# general.net
KiCad netlist of a schematic drawn in EAGLE
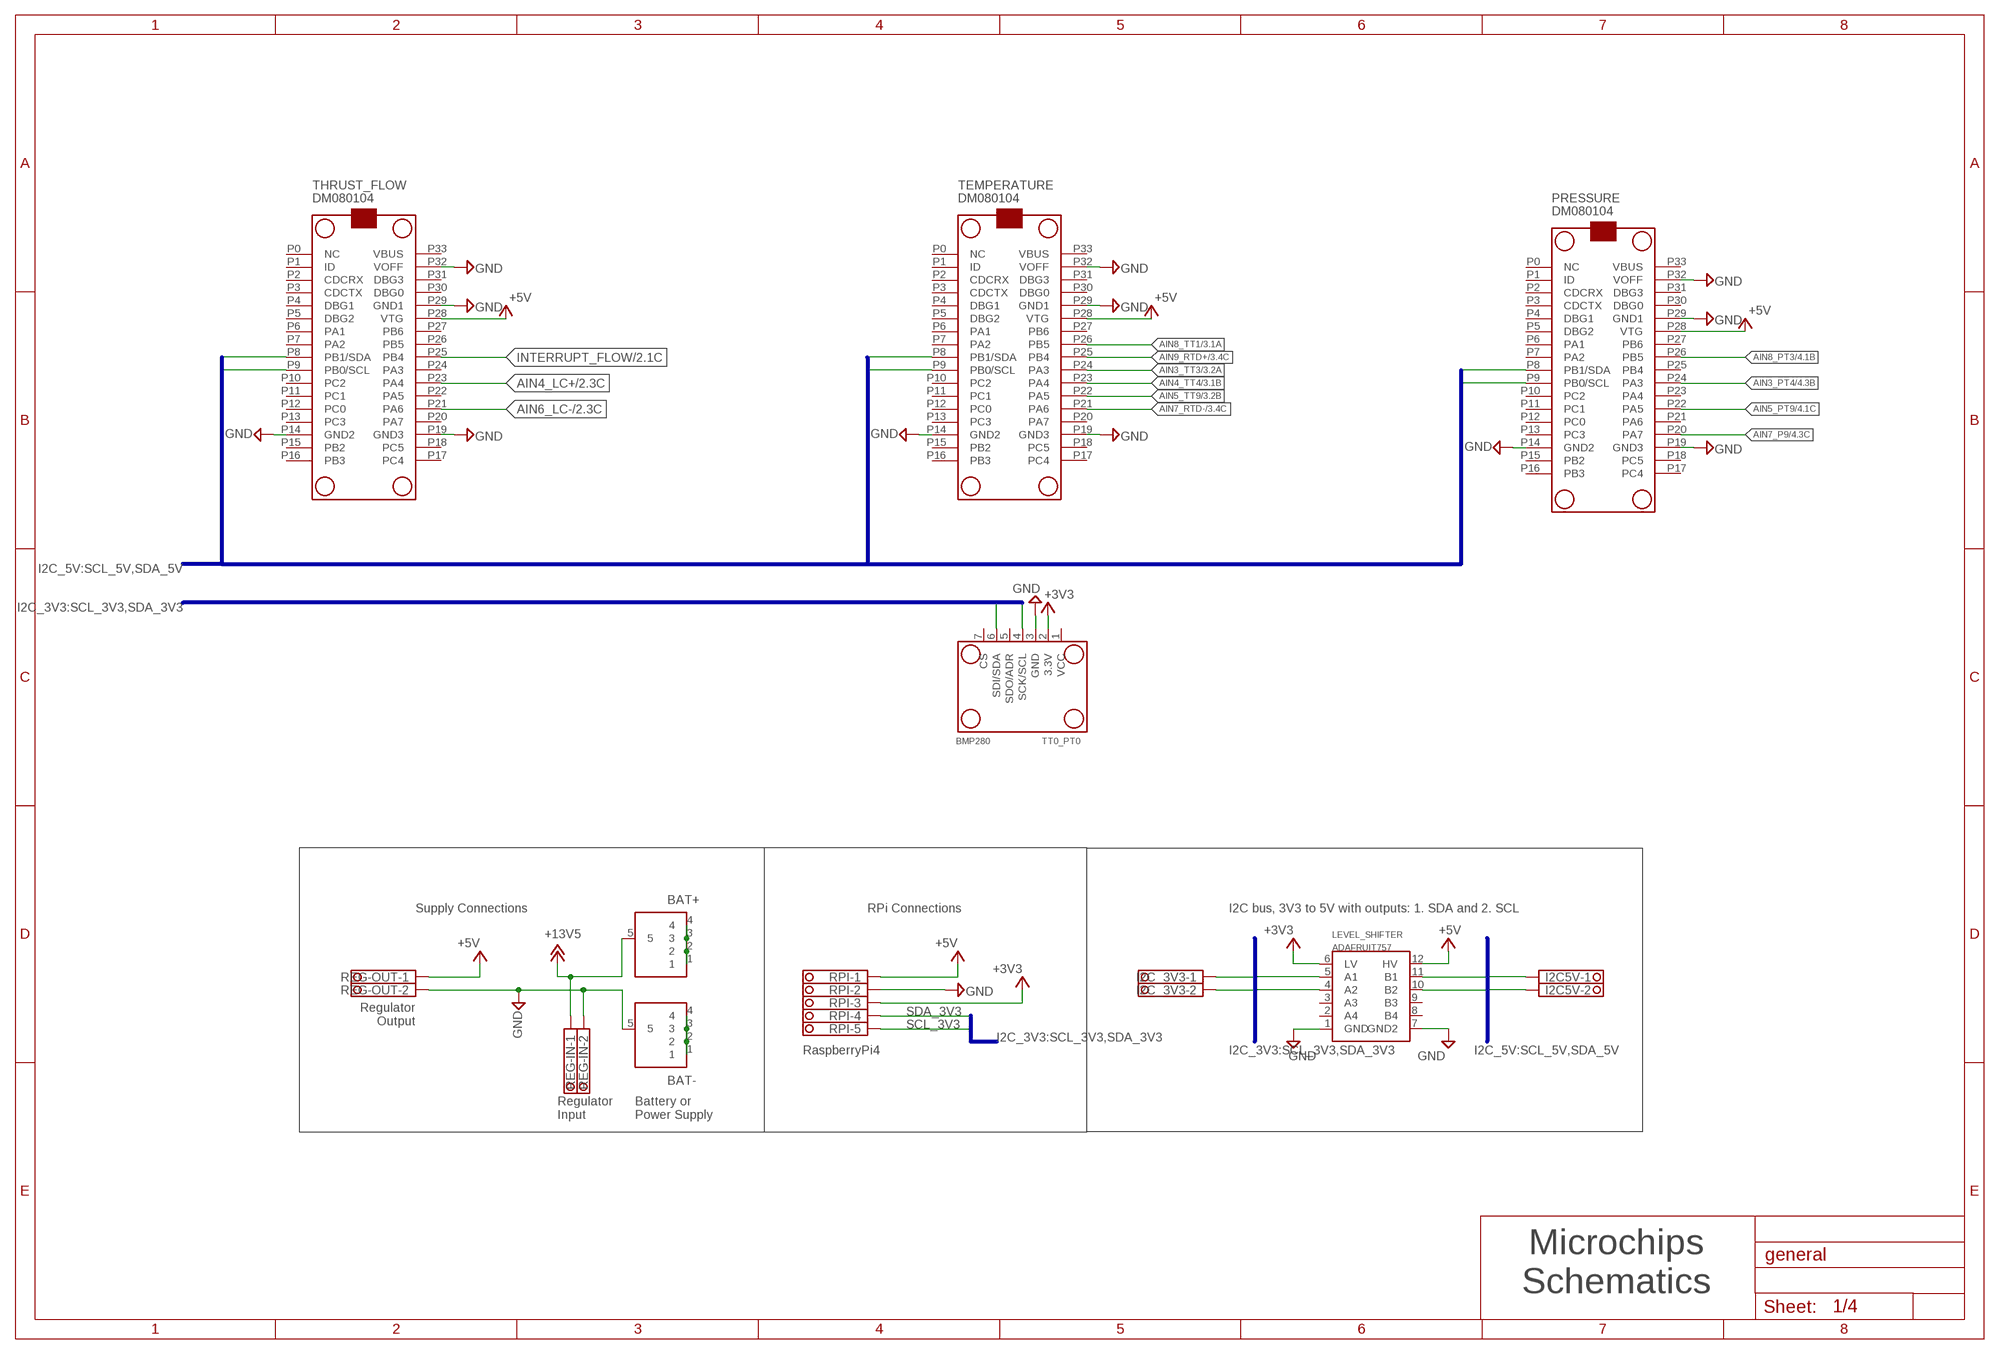
[diagram p0: schematic, sheet 1]
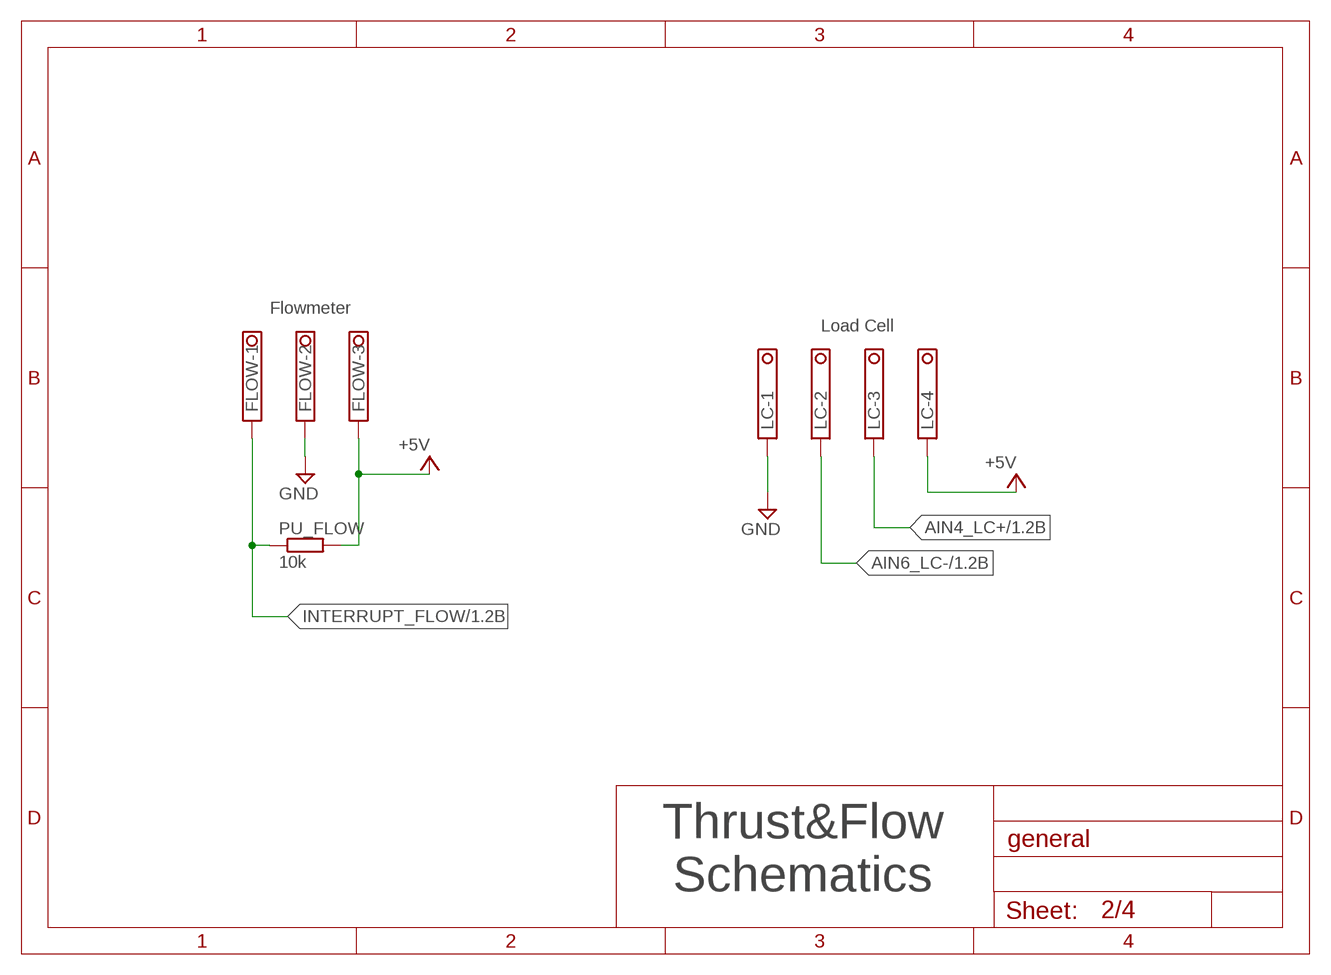
[diagram p1: schematic, sheet 2]
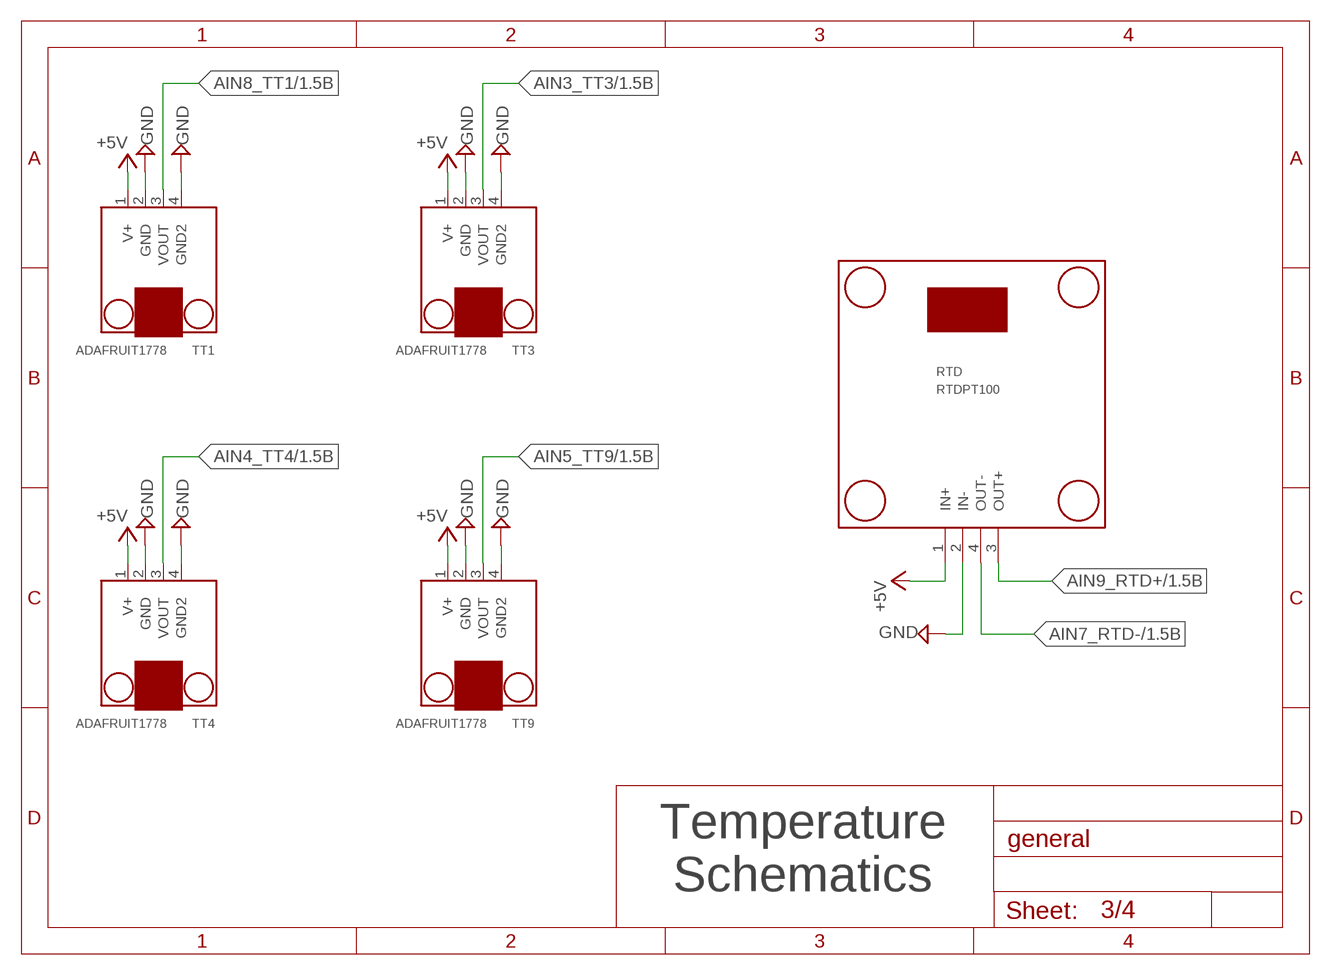
[diagram p2: schematic, sheet 3]
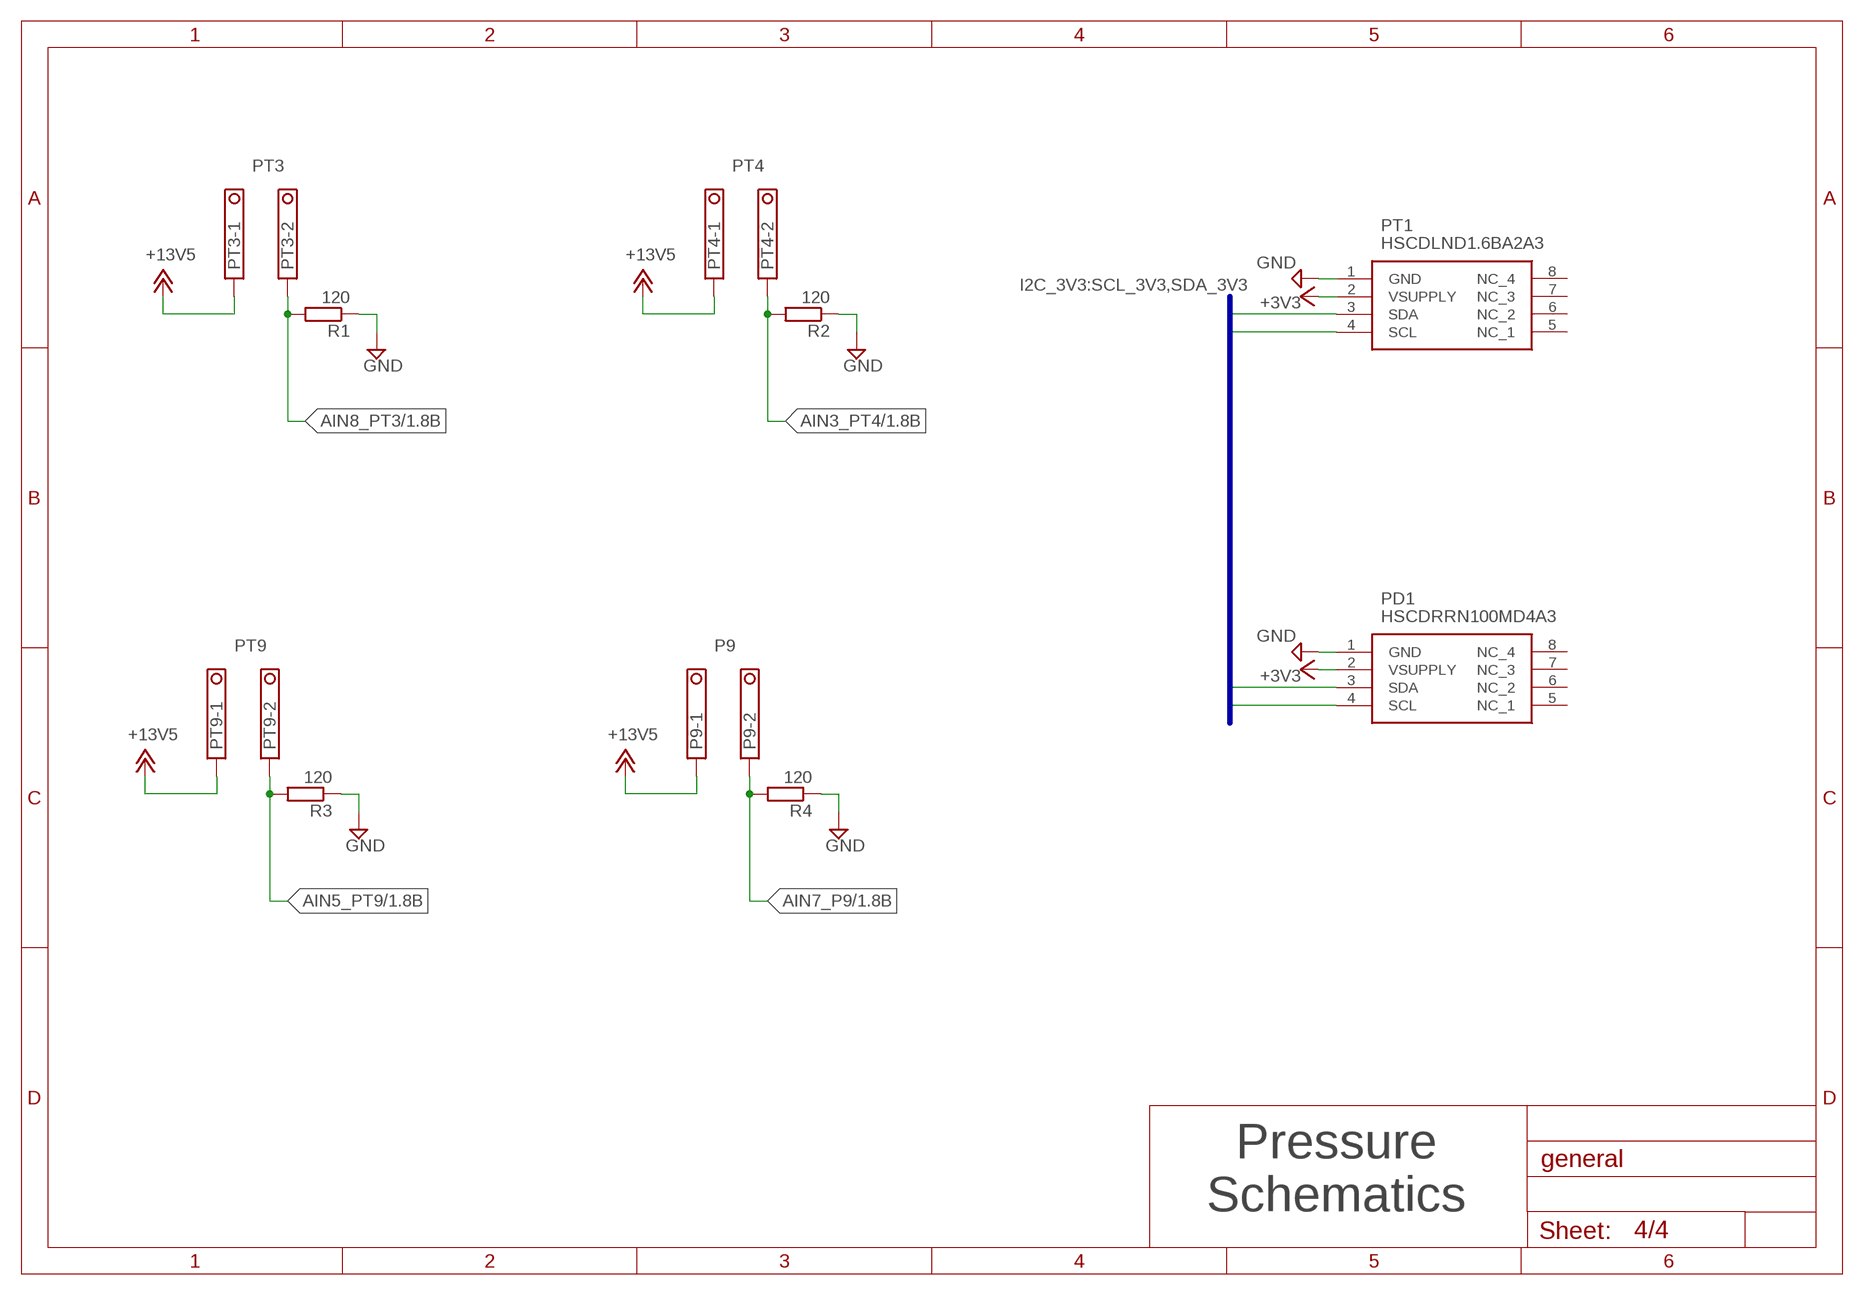
[diagram p3: schematic, sheet 4]

(export (version "E")
  (design (tool "Eeschema 10.0.6"))
  (components
    (comp (ref "RTD")
      (value "RTDPT100")
      (footprint "eagle-import:RTDPT100")
      (libsource (lib "eagle-import") (part "RTDPT100"))
    )
    (comp (ref "TT1")
      (value "ADAFRUIT1778")
      (footprint "eagle-import:ADAFRUIT1778")
      (libsource (lib "eagle-import") (part "ADAFRUIT1778"))
    )
    (comp (ref "TT3")
      (value "ADAFRUIT1778")
      (footprint "eagle-import:ADAFRUIT1778")
      (libsource (lib "eagle-import") (part "ADAFRUIT1778"))
    )
    (comp (ref "TT4")
      (value "ADAFRUIT1778")
      (footprint "eagle-import:ADAFRUIT1778")
      (libsource (lib "eagle-import") (part "ADAFRUIT1778"))
    )
    (comp (ref "TT9")
      (value "ADAFRUIT1778")
      (footprint "eagle-import:ADAFRUIT1778")
      (libsource (lib "eagle-import") (part "ADAFRUIT1778"))
    )
    (comp (ref "FLOW")
      (value "1751251")
      (footprint "eagle-import:1751251")
      (libsource (lib "eagle-import") (part "1751251"))
    )
    (comp (ref "LC")
      (value "1751264")
      (footprint "eagle-import:1751264")
      (libsource (lib "eagle-import") (part "1751264"))
    )
    (comp (ref "PU_FLOW")
      (value "10k")
      (footprint "eagle-import:0207_10")
      (libsource (lib "eagle-import") (part "R-EU_0207/10"))
    )
    (comp (ref "P9")
      (value "1751248")
      (footprint "eagle-import:1751248")
      (libsource (lib "eagle-import") (part "1751248"))
    )
    (comp (ref "PD1")
      (value "HSCDRRN100MD4A3")
      (footprint "eagle-import:HSCDRRN100MD4A3")
      (fields (field (name "MOUSER_PART_NUMBER") "785-HSCDRRN100MD4A3"))
      (libsource (lib "eagle-import") (part "HSCDRRN100MD4A3"))
    )
    (comp (ref "PT1")
      (value "HSCDLND1.6BA2A3")
      (footprint "eagle-import:HSCDLND1.6BA2A3")
      (libsource (lib "eagle-import") (part "HSCDLND1.6BA2A3"))
    )
    (comp (ref "PT3")
      (value "1751248")
      (footprint "eagle-import:1751248")
      (libsource (lib "eagle-import") (part "1751248"))
    )
    (comp (ref "PT4")
      (value "1751248")
      (footprint "eagle-import:1751248")
      (libsource (lib "eagle-import") (part "1751248"))
    )
    (comp (ref "PT9")
      (value "1751248")
      (footprint "eagle-import:1751248")
      (libsource (lib "eagle-import") (part "1751248"))
    )
    (comp (ref "R1")
      (value "120")
      (footprint "eagle-import:0207_10")
      (libsource (lib "eagle-import") (part "R-EU_0207/10"))
    )
    (comp (ref "R2")
      (value "120")
      (footprint "eagle-import:0207_10")
      (libsource (lib "eagle-import") (part "R-EU_0207/10"))
    )
    (comp (ref "R3")
      (value "120")
      (footprint "eagle-import:0207_10")
      (libsource (lib "eagle-import") (part "R-EU_0207/10"))
    )
    (comp (ref "R4")
      (value "120")
      (footprint "eagle-import:0207_10")
      (libsource (lib "eagle-import") (part "R-EU_0207/10"))
    )
    (comp (ref "BAT+")
      (value "73099-2730990")
      (footprint "eagle-import:730990")
      (libsource (lib "eagle-import") (part "73099-2730990"))
    )
    (comp (ref "BAT-")
      (value "73099-0")
      (footprint "eagle-import:730990")
      (fields (field (name "MOUSER_PART_NUMBER") "565-73099-0"))
      (libsource (lib "eagle-import") (part "73099-0"))
    )
    (comp (ref "I2C5V")
      (value "1751248")
      (footprint "eagle-import:1751248")
      (libsource (lib "eagle-import") (part "1751248"))
    )
    (comp (ref "I2C_3V3")
      (value "1751248")
      (footprint "eagle-import:1751248")
      (libsource (lib "eagle-import") (part "1751248"))
    )
    (comp (ref "LEVEL_SHIFTER")
      (value "ADAFRUIT757")
      (footprint "eagle-import:ADAFRUIT757")
      (libsource (lib "eagle-import") (part "ADAFRUIT757"))
    )
    (comp (ref "PRESSURE")
      (value "DM080104")
      (footprint "eagle-import:DM080104")
      (libsource (lib "eagle-import") (part "DM080104"))
    )
    (comp (ref "REG-IN")
      (value "1751248")
      (footprint "eagle-import:1751248")
      (libsource (lib "eagle-import") (part "1751248"))
    )
    (comp (ref "REG-OUT")
      (value "1751248")
      (footprint "eagle-import:1751248")
      (libsource (lib "eagle-import") (part "1751248"))
    )
    (comp (ref "RPI")
      (value "1751277")
      (footprint "eagle-import:1751277")
      (libsource (lib "eagle-import") (part "1751277"))
    )
    (comp (ref "TEMPERATURE")
      (value "DM080104")
      (footprint "eagle-import:DM080104")
      (libsource (lib "eagle-import") (part "DM080104"))
    )
    (comp (ref "THRUST_FLOW")
      (value "DM080104")
      (footprint "eagle-import:DM080104")
      (libsource (lib "eagle-import") (part "DM080104"))
    )
    (comp (ref "TT0_PT0")
      (value "BMP280")
      (footprint "eagle-import:BMP280")
      (libsource (lib "eagle-import") (part "BMP280"))
    )
  )
  (nets
    (net (code "4") (name "+3V3") (class "Default")
      (node (ref "LEVEL_SHIFTER") (pin "6") (pinfunction "LV_6") (pintype "bidirectional"))
      (node (ref "PD1") (pin "2") (pinfunction "VSUPPLY_2") (pintype "power_in"))
      (node (ref "PT1") (pin "2") (pinfunction "VSUPPLY_2") (pintype "power_in"))
      (node (ref "RPI") (pin "3") (pinfunction "K_3") (pintype "passive"))
      (node (ref "TT0_PT0") (pin "2") (pinfunction "3.3V_2") (pintype "power_in"))
    )
    (net (code "5") (name "+5V") (class "Default")
      (node (ref "FLOW") (pin "3") (pinfunction "K_3") (pintype "passive"))
      (node (ref "LC") (pin "4") (pinfunction "K_4") (pintype "passive"))
      (node (ref "LEVEL_SHIFTER") (pin "12") (pinfunction "HV_12") (pintype "bidirectional"))
      (node (ref "PRESSURE") (pin "P28") (pinfunction "VTG_P28") (pintype "power_in"))
      (node (ref "PU_FLOW") (pin "2") (pinfunction "2_2") (pintype "passive"))
      (node (ref "REG-OUT") (pin "1") (pinfunction "K_1") (pintype "passive"))
      (node (ref "RPI") (pin "1") (pinfunction "K_1") (pintype "passive"))
      (node (ref "RTD") (pin "1") (pinfunction "IN+_1") (pintype "input"))
      (node (ref "TEMPERATURE") (pin "P28") (pinfunction "VTG_P28") (pintype "power_in"))
      (node (ref "THRUST_FLOW") (pin "P28") (pinfunction "VTG_P28") (pintype "power_in"))
      (node (ref "TT1") (pin "1") (pinfunction "V+_1") (pintype "power_in"))
      (node (ref "TT3") (pin "1") (pinfunction "V+_1") (pintype "power_in"))
      (node (ref "TT4") (pin "1") (pinfunction "V+_1") (pintype "power_in"))
      (node (ref "TT9") (pin "1") (pinfunction "V+_1") (pintype "power_in"))
    )
    (net (code "6") (name "+13V5") (class "Default")
      (node (ref "BAT+") (pin "5") (pinfunction "5_5") (pintype "bidirectional"))
      (node (ref "P9") (pin "1") (pinfunction "K_1") (pintype "passive"))
      (node (ref "PT3") (pin "1") (pinfunction "K_1") (pintype "passive"))
      (node (ref "PT4") (pin "1") (pinfunction "K_1") (pintype "passive"))
      (node (ref "PT9") (pin "1") (pinfunction "K_1") (pintype "passive"))
      (node (ref "REG-IN") (pin "1") (pinfunction "K_1") (pintype "passive"))
    )
    (net (code "10") (name "AIN3_PT4") (class "Default")
      (node (ref "PRESSURE") (pin "P24") (pinfunction "PA3_P24") (pintype "bidirectional"))
      (node (ref "PT4") (pin "2") (pinfunction "K_2") (pintype "passive"))
      (node (ref "R2") (pin "2") (pinfunction "2_2") (pintype "passive"))
    )
    (net (code "11") (name "AIN3_TT3") (class "Default")
      (node (ref "TEMPERATURE") (pin "P24") (pinfunction "PA3_P24") (pintype "bidirectional"))
      (node (ref "TT3") (pin "3") (pinfunction "VOUT_3") (pintype "output"))
    )
    (net (code "12") (name "AIN4_LC+") (class "Default")
      (node (ref "LC") (pin "3") (pinfunction "K_3") (pintype "passive"))
      (node (ref "THRUST_FLOW") (pin "P23") (pinfunction "PA4_P23") (pintype "bidirectional"))
    )
    (net (code "13") (name "AIN4_TT4") (class "Default")
      (node (ref "TEMPERATURE") (pin "P23") (pinfunction "PA4_P23") (pintype "bidirectional"))
      (node (ref "TT4") (pin "3") (pinfunction "VOUT_3") (pintype "output"))
    )
    (net (code "14") (name "AIN5_PT9") (class "Default")
      (node (ref "PRESSURE") (pin "P22") (pinfunction "PA5_P22") (pintype "bidirectional"))
      (node (ref "PT9") (pin "2") (pinfunction "K_2") (pintype "passive"))
      (node (ref "R3") (pin "2") (pinfunction "2_2") (pintype "passive"))
    )
    (net (code "15") (name "AIN5_TT9") (class "Default")
      (node (ref "TEMPERATURE") (pin "P22") (pinfunction "PA5_P22") (pintype "bidirectional"))
      (node (ref "TT9") (pin "3") (pinfunction "VOUT_3") (pintype "output"))
    )
    (net (code "16") (name "AIN6_LC-") (class "Default")
      (node (ref "LC") (pin "2") (pinfunction "K_2") (pintype "passive"))
      (node (ref "THRUST_FLOW") (pin "P21") (pinfunction "PA6_P21") (pintype "bidirectional"))
    )
    (net (code "17") (name "AIN7_P9") (class "Default")
      (node (ref "P9") (pin "2") (pinfunction "K_2") (pintype "passive"))
      (node (ref "PRESSURE") (pin "P20") (pinfunction "PA7_P20") (pintype "bidirectional"))
      (node (ref "R4") (pin "2") (pinfunction "2_2") (pintype "passive"))
    )
    (net (code "18") (name "AIN7_RTD-") (class "Default")
      (node (ref "RTD") (pin "4") (pinfunction "OUT-_4") (pintype "output"))
      (node (ref "TEMPERATURE") (pin "P21") (pinfunction "PA6_P21") (pintype "bidirectional"))
    )
    (net (code "19") (name "AIN8_PT3") (class "Default")
      (node (ref "PRESSURE") (pin "P26") (pinfunction "PB5_P26") (pintype "bidirectional"))
      (node (ref "PT3") (pin "2") (pinfunction "K_2") (pintype "passive"))
      (node (ref "R1") (pin "2") (pinfunction "2_2") (pintype "passive"))
    )
    (net (code "20") (name "AIN8_TT1") (class "Default")
      (node (ref "TEMPERATURE") (pin "P26") (pinfunction "PB5_P26") (pintype "bidirectional"))
      (node (ref "TT1") (pin "3") (pinfunction "VOUT_3") (pintype "output"))
    )
    (net (code "21") (name "AIN9_RTD+") (class "Default")
      (node (ref "RTD") (pin "3") (pinfunction "OUT+_3") (pintype "output"))
      (node (ref "TEMPERATURE") (pin "P25") (pinfunction "PB4_P25") (pintype "bidirectional"))
    )
    (net (code "22") (name "GND") (class "Default")
      (node (ref "BAT-") (pin "5") (pinfunction "5_5") (pintype "bidirectional"))
      (node (ref "FLOW") (pin "2") (pinfunction "K_2") (pintype "passive"))
      (node (ref "LC") (pin "1") (pinfunction "K_1") (pintype "passive"))
      (node (ref "LEVEL_SHIFTER") (pin "1") (pinfunction "GND_1") (pintype "bidirectional"))
      (node (ref "LEVEL_SHIFTER") (pin "7") (pinfunction "GND2_7") (pintype "bidirectional"))
      (node (ref "PD1") (pin "1") (pinfunction "GND_1") (pintype "power_in"))
      (node (ref "PRESSURE") (pin "P14") (pinfunction "GND2_P14") (pintype "bidirectional"))
      (node (ref "PRESSURE") (pin "P19") (pinfunction "GND3_P19") (pintype "bidirectional"))
      (node (ref "PRESSURE") (pin "P29") (pinfunction "GND1_P29") (pintype "power_in"))
      (node (ref "PRESSURE") (pin "P32") (pinfunction "VOFF_P32") (pintype "power_in"))
      (node (ref "PT1") (pin "1") (pinfunction "GND_1") (pintype "power_in"))
      (node (ref "R1") (pin "1") (pinfunction "1_1") (pintype "passive"))
      (node (ref "R2") (pin "1") (pinfunction "1_1") (pintype "passive"))
      (node (ref "R3") (pin "1") (pinfunction "1_1") (pintype "passive"))
      (node (ref "R4") (pin "1") (pinfunction "1_1") (pintype "passive"))
      (node (ref "REG-IN") (pin "2") (pinfunction "K_2") (pintype "passive"))
      (node (ref "REG-OUT") (pin "2") (pinfunction "K_2") (pintype "passive"))
      (node (ref "RPI") (pin "2") (pinfunction "K_2") (pintype "passive"))
      (node (ref "RTD") (pin "2") (pinfunction "IN-_2") (pintype "input"))
      (node (ref "TEMPERATURE") (pin "P14") (pinfunction "GND2_P14") (pintype "bidirectional"))
      (node (ref "TEMPERATURE") (pin "P19") (pinfunction "GND3_P19") (pintype "bidirectional"))
      (node (ref "TEMPERATURE") (pin "P29") (pinfunction "GND1_P29") (pintype "power_in"))
      (node (ref "TEMPERATURE") (pin "P32") (pinfunction "VOFF_P32") (pintype "power_in"))
      (node (ref "THRUST_FLOW") (pin "P14") (pinfunction "GND2_P14") (pintype "bidirectional"))
      (node (ref "THRUST_FLOW") (pin "P19") (pinfunction "GND3_P19") (pintype "bidirectional"))
      (node (ref "THRUST_FLOW") (pin "P29") (pinfunction "GND1_P29") (pintype "power_in"))
      (node (ref "THRUST_FLOW") (pin "P32") (pinfunction "VOFF_P32") (pintype "power_in"))
      (node (ref "TT0_PT0") (pin "3") (pinfunction "GND_3") (pintype "power_in"))
      (node (ref "TT1") (pin "2") (pinfunction "GND_2") (pintype "power_in"))
      (node (ref "TT1") (pin "4") (pinfunction "GND2_4") (pintype "power_in"))
      (node (ref "TT3") (pin "2") (pinfunction "GND_2") (pintype "power_in"))
      (node (ref "TT3") (pin "4") (pinfunction "GND2_4") (pintype "power_in"))
      (node (ref "TT4") (pin "2") (pinfunction "GND_2") (pintype "power_in"))
      (node (ref "TT4") (pin "4") (pinfunction "GND2_4") (pintype "power_in"))
      (node (ref "TT9") (pin "2") (pinfunction "GND_2") (pintype "power_in"))
      (node (ref "TT9") (pin "4") (pinfunction "GND2_4") (pintype "power_in"))
    )
    (net (code "23") (name "INTERRUPT_FLOW") (class "Default")
      (node (ref "FLOW") (pin "1") (pinfunction "K_1") (pintype "passive"))
      (node (ref "PU_FLOW") (pin "1") (pinfunction "1_1") (pintype "passive"))
      (node (ref "THRUST_FLOW") (pin "P25") (pinfunction "PB4_P25") (pintype "bidirectional"))
    )
    (net (code "24") (name "Net-(BAT+-Pad1)") (class "Default")
      (node (ref "BAT+") (pin "1") (pinfunction "1_1") (pintype "bidirectional"))
      (node (ref "BAT+") (pin "2") (pinfunction "2_2") (pintype "bidirectional"))
      (node (ref "BAT+") (pin "3") (pinfunction "3_3") (pintype "bidirectional"))
      (node (ref "BAT+") (pin "4") (pinfunction "4_4") (pintype "bidirectional"))
    )
    (net (code "25") (name "Net-(BAT--Pad1)") (class "Default")
      (node (ref "BAT-") (pin "1") (pinfunction "1_1") (pintype "bidirectional"))
      (node (ref "BAT-") (pin "2") (pinfunction "2_2") (pintype "bidirectional"))
      (node (ref "BAT-") (pin "3") (pinfunction "3_3") (pintype "bidirectional"))
      (node (ref "BAT-") (pin "4") (pinfunction "4_4") (pintype "bidirectional"))
    )
    (net (code "26") (name "SCL_3V3") (class "Default")
      (node (ref "I2C_3V3") (pin "2") (pinfunction "K_2") (pintype "passive"))
      (node (ref "LEVEL_SHIFTER") (pin "4") (pinfunction "A2_4") (pintype "bidirectional"))
      (node (ref "PD1") (pin "4") (pinfunction "SCL_4") (pintype "bidirectional"))
      (node (ref "PT1") (pin "4") (pinfunction "SCL_4") (pintype "bidirectional"))
      (node (ref "RPI") (pin "5") (pinfunction "K_5") (pintype "passive"))
      (node (ref "TT0_PT0") (pin "4") (pinfunction "SCK/SCL_4") (pintype "bidirectional"))
    )
    (net (code "27") (name "SCL_5V") (class "Default")
      (node (ref "I2C5V") (pin "2") (pinfunction "K_2") (pintype "passive"))
      (node (ref "LEVEL_SHIFTER") (pin "10") (pinfunction "B2_10") (pintype "bidirectional"))
      (node (ref "PRESSURE") (pin "P9") (pinfunction "PB0/SCL_P9") (pintype "bidirectional"))
      (node (ref "TEMPERATURE") (pin "P9") (pinfunction "PB0/SCL_P9") (pintype "bidirectional"))
      (node (ref "THRUST_FLOW") (pin "P9") (pinfunction "PB0/SCL_P9") (pintype "bidirectional"))
    )
    (net (code "28") (name "SDA_3V3") (class "Default")
      (node (ref "I2C_3V3") (pin "1") (pinfunction "K_1") (pintype "passive"))
      (node (ref "LEVEL_SHIFTER") (pin "5") (pinfunction "A1_5") (pintype "bidirectional"))
      (node (ref "PD1") (pin "3") (pinfunction "SDA_3") (pintype "bidirectional"))
      (node (ref "PT1") (pin "3") (pinfunction "SDA_3") (pintype "bidirectional"))
      (node (ref "RPI") (pin "4") (pinfunction "K_4") (pintype "passive"))
      (node (ref "TT0_PT0") (pin "6") (pinfunction "SDI/SDA_6") (pintype "bidirectional"))
    )
    (net (code "29") (name "SDA_5V") (class "Default")
      (node (ref "I2C5V") (pin "1") (pinfunction "K_1") (pintype "passive"))
      (node (ref "LEVEL_SHIFTER") (pin "11") (pinfunction "B1_11") (pintype "bidirectional"))
      (node (ref "PRESSURE") (pin "P8") (pinfunction "PB1/SDA_P8") (pintype "bidirectional"))
      (node (ref "TEMPERATURE") (pin "P8") (pinfunction "PB1/SDA_P8") (pintype "bidirectional"))
      (node (ref "THRUST_FLOW") (pin "P8") (pinfunction "PB1/SDA_P8") (pintype "bidirectional"))
    )
    (net (code "30") (name "VCC") (class "Default")
      (node (ref "TT0_PT0") (pin "1") (pinfunction "VCC_1") (pintype "power_in"))
    )
    (net (code "31") (name "unconnected-(LEVEL_SHIFTER-A3-Pad3)") (class "Default")
      (node (ref "LEVEL_SHIFTER") (pin "3") (pinfunction "A3_3") (pintype "bidirectional"))
    )
    (net (code "32") (name "unconnected-(LEVEL_SHIFTER-A4-Pad2)") (class "Default")
      (node (ref "LEVEL_SHIFTER") (pin "2") (pinfunction "A4_2") (pintype "bidirectional"))
    )
    (net (code "33") (name "unconnected-(LEVEL_SHIFTER-B3-Pad9)") (class "Default")
      (node (ref "LEVEL_SHIFTER") (pin "9") (pinfunction "B3_9") (pintype "bidirectional"))
    )
    (net (code "34") (name "unconnected-(LEVEL_SHIFTER-B4-Pad8)") (class "Default")
      (node (ref "LEVEL_SHIFTER") (pin "8") (pinfunction "B4_8") (pintype "bidirectional"))
    )
    (net (code "35") (name "unconnected-(PD1-NC_1-Pad5)") (class "Default")
      (node (ref "PD1") (pin "5") (pinfunction "NC_1_5") (pintype "no_connect"))
    )
    (net (code "36") (name "unconnected-(PD1-NC_2-Pad6)") (class "Default")
      (node (ref "PD1") (pin "6") (pinfunction "NC_2_6") (pintype "no_connect"))
    )
    (net (code "37") (name "unconnected-(PD1-NC_3-Pad7)") (class "Default")
      (node (ref "PD1") (pin "7") (pinfunction "NC_3_7") (pintype "no_connect"))
    )
    (net (code "38") (name "unconnected-(PD1-NC_4-Pad8)") (class "Default")
      (node (ref "PD1") (pin "8") (pinfunction "NC_4_8") (pintype "no_connect"))
    )
    (net (code "39") (name "unconnected-(PRESSURE-CDCRX-PadP2)") (class "Default")
      (node (ref "PRESSURE") (pin "P2") (pinfunction "CDCRX_P2") (pintype "bidirectional"))
    )
    (net (code "40") (name "unconnected-(PRESSURE-CDCTX-PadP3)") (class "Default")
      (node (ref "PRESSURE") (pin "P3") (pinfunction "CDCTX_P3") (pintype "bidirectional"))
    )
    (net (code "41") (name "unconnected-(PRESSURE-DBG0-PadP30)") (class "Default")
      (node (ref "PRESSURE") (pin "P30") (pinfunction "DBG0_P30") (pintype "no_connect"))
    )
    (net (code "42") (name "unconnected-(PRESSURE-DBG1-PadP4)") (class "Default")
      (node (ref "PRESSURE") (pin "P4") (pinfunction "DBG1_P4") (pintype "no_connect"))
    )
    (net (code "43") (name "unconnected-(PRESSURE-DBG2-PadP5)") (class "Default")
      (node (ref "PRESSURE") (pin "P5") (pinfunction "DBG2_P5") (pintype "no_connect"))
    )
    (net (code "44") (name "unconnected-(PRESSURE-DBG3-PadP31)") (class "Default")
      (node (ref "PRESSURE") (pin "P31") (pinfunction "DBG3_P31") (pintype "no_connect"))
    )
    (net (code "45") (name "unconnected-(PRESSURE-ID-PadP1)") (class "Default")
      (node (ref "PRESSURE") (pin "P1") (pinfunction "ID_P1") (pintype "output"))
    )
    (net (code "46") (name "unconnected-(PRESSURE-NC-PadP0)") (class "Default")
      (node (ref "PRESSURE") (pin "P0") (pinfunction "NC_P0") (pintype "no_connect"))
    )
    (net (code "47") (name "unconnected-(PRESSURE-PA1-PadP6)") (class "Default")
      (node (ref "PRESSURE") (pin "P6") (pinfunction "PA1_P6") (pintype "bidirectional"))
    )
    (net (code "48") (name "unconnected-(PRESSURE-PA2-PadP7)") (class "Default")
      (node (ref "PRESSURE") (pin "P7") (pinfunction "PA2_P7") (pintype "bidirectional"))
    )
    (net (code "49") (name "unconnected-(PRESSURE-PA4-PadP23)") (class "Default")
      (node (ref "PRESSURE") (pin "P23") (pinfunction "PA4_P23") (pintype "bidirectional"))
    )
    (net (code "50") (name "unconnected-(PRESSURE-PA6-PadP21)") (class "Default")
      (node (ref "PRESSURE") (pin "P21") (pinfunction "PA6_P21") (pintype "bidirectional"))
    )
    (net (code "51") (name "unconnected-(PRESSURE-PB2-PadP15)") (class "Default")
      (node (ref "PRESSURE") (pin "P15") (pinfunction "PB2_P15") (pintype "bidirectional"))
    )
    (net (code "52") (name "unconnected-(PRESSURE-PB3-PadP16)") (class "Default")
      (node (ref "PRESSURE") (pin "P16") (pinfunction "PB3_P16") (pintype "bidirectional"))
    )
    (net (code "53") (name "unconnected-(PRESSURE-PB4-PadP25)") (class "Default")
      (node (ref "PRESSURE") (pin "P25") (pinfunction "PB4_P25") (pintype "bidirectional"))
    )
    (net (code "54") (name "unconnected-(PRESSURE-PB6-PadP27)") (class "Default")
      (node (ref "PRESSURE") (pin "P27") (pinfunction "PB6_P27") (pintype "bidirectional"))
    )
    (net (code "55") (name "unconnected-(PRESSURE-PC0-PadP12)") (class "Default")
      (node (ref "PRESSURE") (pin "P12") (pinfunction "PC0_P12") (pintype "bidirectional"))
    )
    (net (code "56") (name "unconnected-(PRESSURE-PC1-PadP11)") (class "Default")
      (node (ref "PRESSURE") (pin "P11") (pinfunction "PC1_P11") (pintype "bidirectional"))
    )
    (net (code "57") (name "unconnected-(PRESSURE-PC2-PadP10)") (class "Default")
      (node (ref "PRESSURE") (pin "P10") (pinfunction "PC2_P10") (pintype "bidirectional"))
    )
    (net (code "58") (name "unconnected-(PRESSURE-PC3-PadP13)") (class "Default")
      (node (ref "PRESSURE") (pin "P13") (pinfunction "PC3_P13") (pintype "bidirectional"))
    )
    (net (code "59") (name "unconnected-(PRESSURE-PC4-PadP17)") (class "Default")
      (node (ref "PRESSURE") (pin "P17") (pinfunction "PC4_P17") (pintype "bidirectional"))
    )
    (net (code "60") (name "unconnected-(PRESSURE-PC5-PadP18)") (class "Default")
      (node (ref "PRESSURE") (pin "P18") (pinfunction "PC5_P18") (pintype "bidirectional"))
    )
    (net (code "61") (name "unconnected-(PRESSURE-VBUS-PadP33)") (class "Default")
      (node (ref "PRESSURE") (pin "P33") (pinfunction "VBUS_P33") (pintype "output"))
    )
    (net (code "62") (name "unconnected-(PT1-NC_1-Pad5)") (class "Default")
      (node (ref "PT1") (pin "5") (pinfunction "NC_1_5") (pintype "no_connect"))
    )
    (net (code "63") (name "unconnected-(PT1-NC_2-Pad6)") (class "Default")
      (node (ref "PT1") (pin "6") (pinfunction "NC_2_6") (pintype "no_connect"))
    )
    (net (code "64") (name "unconnected-(PT1-NC_3-Pad7)") (class "Default")
      (node (ref "PT1") (pin "7") (pinfunction "NC_3_7") (pintype "no_connect"))
    )
    (net (code "65") (name "unconnected-(PT1-NC_4-Pad8)") (class "Default")
      (node (ref "PT1") (pin "8") (pinfunction "NC_4_8") (pintype "no_connect"))
    )
    (net (code "66") (name "unconnected-(TEMPERATURE-CDCRX-PadP2)") (class "Default")
      (node (ref "TEMPERATURE") (pin "P2") (pinfunction "CDCRX_P2") (pintype "bidirectional"))
    )
    (net (code "67") (name "unconnected-(TEMPERATURE-CDCTX-PadP3)") (class "Default")
      (node (ref "TEMPERATURE") (pin "P3") (pinfunction "CDCTX_P3") (pintype "bidirectional"))
    )
    (net (code "68") (name "unconnected-(TEMPERATURE-DBG0-PadP30)") (class "Default")
      (node (ref "TEMPERATURE") (pin "P30") (pinfunction "DBG0_P30") (pintype "no_connect"))
    )
    (net (code "69") (name "unconnected-(TEMPERATURE-DBG1-PadP4)") (class "Default")
      (node (ref "TEMPERATURE") (pin "P4") (pinfunction "DBG1_P4") (pintype "no_connect"))
    )
    (net (code "70") (name "unconnected-(TEMPERATURE-DBG2-PadP5)") (class "Default")
      (node (ref "TEMPERATURE") (pin "P5") (pinfunction "DBG2_P5") (pintype "no_connect"))
    )
    (net (code "71") (name "unconnected-(TEMPERATURE-DBG3-PadP31)") (class "Default")
      (node (ref "TEMPERATURE") (pin "P31") (pinfunction "DBG3_P31") (pintype "no_connect"))
    )
    (net (code "72") (name "unconnected-(TEMPERATURE-ID-PadP1)") (class "Default")
      (node (ref "TEMPERATURE") (pin "P1") (pinfunction "ID_P1") (pintype "output"))
    )
    (net (code "73") (name "unconnected-(TEMPERATURE-NC-PadP0)") (class "Default")
      (node (ref "TEMPERATURE") (pin "P0") (pinfunction "NC_P0") (pintype "no_connect"))
    )
    (net (code "74") (name "unconnected-(TEMPERATURE-PA1-PadP6)") (class "Default")
      (node (ref "TEMPERATURE") (pin "P6") (pinfunction "PA1_P6") (pintype "bidirectional"))
    )
    (net (code "75") (name "unconnected-(TEMPERATURE-PA2-PadP7)") (class "Default")
      (node (ref "TEMPERATURE") (pin "P7") (pinfunction "PA2_P7") (pintype "bidirectional"))
    )
    (net (code "76") (name "unconnected-(TEMPERATURE-PA7-PadP20)") (class "Default")
      (node (ref "TEMPERATURE") (pin "P20") (pinfunction "PA7_P20") (pintype "bidirectional"))
    )
    (net (code "77") (name "unconnected-(TEMPERATURE-PB2-PadP15)") (class "Default")
      (node (ref "TEMPERATURE") (pin "P15") (pinfunction "PB2_P15") (pintype "bidirectional"))
    )
    (net (code "78") (name "unconnected-(TEMPERATURE-PB3-PadP16)") (class "Default")
      (node (ref "TEMPERATURE") (pin "P16") (pinfunction "PB3_P16") (pintype "bidirectional"))
    )
    (net (code "79") (name "unconnected-(TEMPERATURE-PB6-PadP27)") (class "Default")
      (node (ref "TEMPERATURE") (pin "P27") (pinfunction "PB6_P27") (pintype "bidirectional"))
    )
    (net (code "80") (name "unconnected-(TEMPERATURE-PC0-PadP12)") (class "Default")
      (node (ref "TEMPERATURE") (pin "P12") (pinfunction "PC0_P12") (pintype "bidirectional"))
    )
    (net (code "81") (name "unconnected-(TEMPERATURE-PC1-PadP11)") (class "Default")
      (node (ref "TEMPERATURE") (pin "P11") (pinfunction "PC1_P11") (pintype "bidirectional"))
    )
    (net (code "82") (name "unconnected-(TEMPERATURE-PC2-PadP10)") (class "Default")
      (node (ref "TEMPERATURE") (pin "P10") (pinfunction "PC2_P10") (pintype "bidirectional"))
    )
    (net (code "83") (name "unconnected-(TEMPERATURE-PC3-PadP13)") (class "Default")
      (node (ref "TEMPERATURE") (pin "P13") (pinfunction "PC3_P13") (pintype "bidirectional"))
    )
    (net (code "84") (name "unconnected-(TEMPERATURE-PC4-PadP17)") (class "Default")
      (node (ref "TEMPERATURE") (pin "P17") (pinfunction "PC4_P17") (pintype "bidirectional"))
    )
    (net (code "85") (name "unconnected-(TEMPERATURE-PC5-PadP18)") (class "Default")
      (node (ref "TEMPERATURE") (pin "P18") (pinfunction "PC5_P18") (pintype "bidirectional"))
    )
    (net (code "86") (name "unconnected-(TEMPERATURE-VBUS-PadP33)") (class "Default")
      (node (ref "TEMPERATURE") (pin "P33") (pinfunction "VBUS_P33") (pintype "output"))
    )
    (net (code "87") (name "unconnected-(THRUST_FLOW-CDCRX-PadP2)") (class "Default")
      (node (ref "THRUST_FLOW") (pin "P2") (pinfunction "CDCRX_P2") (pintype "bidirectional"))
    )
    (net (code "88") (name "unconnected-(THRUST_FLOW-CDCTX-PadP3)") (class "Default")
      (node (ref "THRUST_FLOW") (pin "P3") (pinfunction "CDCTX_P3") (pintype "bidirectional"))
    )
    (net (code "89") (name "unconnected-(THRUST_FLOW-DBG0-PadP30)") (class "Default")
      (node (ref "THRUST_FLOW") (pin "P30") (pinfunction "DBG0_P30") (pintype "no_connect"))
    )
    (net (code "90") (name "unconnected-(THRUST_FLOW-DBG1-PadP4)") (class "Default")
      (node (ref "THRUST_FLOW") (pin "P4") (pinfunction "DBG1_P4") (pintype "no_connect"))
    )
    (net (code "91") (name "unconnected-(THRUST_FLOW-DBG2-PadP5)") (class "Default")
      (node (ref "THRUST_FLOW") (pin "P5") (pinfunction "DBG2_P5") (pintype "no_connect"))
    )
    (net (code "92") (name "unconnected-(THRUST_FLOW-DBG3-PadP31)") (class "Default")
      (node (ref "THRUST_FLOW") (pin "P31") (pinfunction "DBG3_P31") (pintype "no_connect"))
    )
    (net (code "93") (name "unconnected-(THRUST_FLOW-ID-PadP1)") (class "Default")
      (node (ref "THRUST_FLOW") (pin "P1") (pinfunction "ID_P1") (pintype "output"))
    )
    (net (code "94") (name "unconnected-(THRUST_FLOW-NC-PadP0)") (class "Default")
      (node (ref "THRUST_FLOW") (pin "P0") (pinfunction "NC_P0") (pintype "no_connect"))
    )
    (net (code "95") (name "unconnected-(THRUST_FLOW-PA1-PadP6)") (class "Default")
      (node (ref "THRUST_FLOW") (pin "P6") (pinfunction "PA1_P6") (pintype "bidirectional"))
    )
    (net (code "96") (name "unconnected-(THRUST_FLOW-PA2-PadP7)") (class "Default")
      (node (ref "THRUST_FLOW") (pin "P7") (pinfunction "PA2_P7") (pintype "bidirectional"))
    )
    (net (code "97") (name "unconnected-(THRUST_FLOW-PA3-PadP24)") (class "Default")
      (node (ref "THRUST_FLOW") (pin "P24") (pinfunction "PA3_P24") (pintype "bidirectional"))
    )
    (net (code "98") (name "unconnected-(THRUST_FLOW-PA5-PadP22)") (class "Default")
      (node (ref "THRUST_FLOW") (pin "P22") (pinfunction "PA5_P22") (pintype "bidirectional"))
    )
    (net (code "99") (name "unconnected-(THRUST_FLOW-PA7-PadP20)") (class "Default")
      (node (ref "THRUST_FLOW") (pin "P20") (pinfunction "PA7_P20") (pintype "bidirectional"))
    )
    (net (code "100") (name "unconnected-(THRUST_FLOW-PB2-PadP15)") (class "Default")
      (node (ref "THRUST_FLOW") (pin "P15") (pinfunction "PB2_P15") (pintype "bidirectional"))
    )
    (net (code "101") (name "unconnected-(THRUST_FLOW-PB3-PadP16)") (class "Default")
      (node (ref "THRUST_FLOW") (pin "P16") (pinfunction "PB3_P16") (pintype "bidirectional"))
    )
    (net (code "102") (name "unconnected-(THRUST_FLOW-PB5-PadP26)") (class "Default")
      (node (ref "THRUST_FLOW") (pin "P26") (pinfunction "PB5_P26") (pintype "bidirectional"))
    )
    (net (code "103") (name "unconnected-(THRUST_FLOW-PB6-PadP27)") (class "Default")
      (node (ref "THRUST_FLOW") (pin "P27") (pinfunction "PB6_P27") (pintype "bidirectional"))
    )
    (net (code "104") (name "unconnected-(THRUST_FLOW-PC0-PadP12)") (class "Default")
      (node (ref "THRUST_FLOW") (pin "P12") (pinfunction "PC0_P12") (pintype "bidirectional"))
    )
    (net (code "105") (name "unconnected-(THRUST_FLOW-PC1-PadP11)") (class "Default")
      (node (ref "THRUST_FLOW") (pin "P11") (pinfunction "PC1_P11") (pintype "bidirectional"))
    )
    (net (code "106") (name "unconnected-(THRUST_FLOW-PC2-PadP10)") (class "Default")
      (node (ref "THRUST_FLOW") (pin "P10") (pinfunction "PC2_P10") (pintype "bidirectional"))
    )
    (net (code "107") (name "unconnected-(THRUST_FLOW-PC3-PadP13)") (class "Default")
      (node (ref "THRUST_FLOW") (pin "P13") (pinfunction "PC3_P13") (pintype "bidirectional"))
    )
    (net (code "108") (name "unconnected-(THRUST_FLOW-PC4-PadP17)") (class "Default")
      (node (ref "THRUST_FLOW") (pin "P17") (pinfunction "PC4_P17") (pintype "bidirectional"))
    )
    (net (code "109") (name "unconnected-(THRUST_FLOW-PC5-PadP18)") (class "Default")
      (node (ref "THRUST_FLOW") (pin "P18") (pinfunction "PC5_P18") (pintype "bidirectional"))
    )
    (net (code "110") (name "unconnected-(THRUST_FLOW-VBUS-PadP33)") (class "Default")
      (node (ref "THRUST_FLOW") (pin "P33") (pinfunction "VBUS_P33") (pintype "output"))
    )
    (net (code "111") (name "unconnected-(TT0_PT0-CS-Pad7)") (class "Default")
      (node (ref "TT0_PT0") (pin "7") (pinfunction "CS_7") (pintype "bidirectional"))
    )
    (net (code "112") (name "unconnected-(TT0_PT0-SDO{slash}ADR-Pad5)") (class "Default")
      (node (ref "TT0_PT0") (pin "5") (pinfunction "SDO/ADR_5") (pintype "bidirectional"))
    )
  )
)
